# SCH_snow_light.net
KiCad netlist of a schematic drawn in EasyEDA
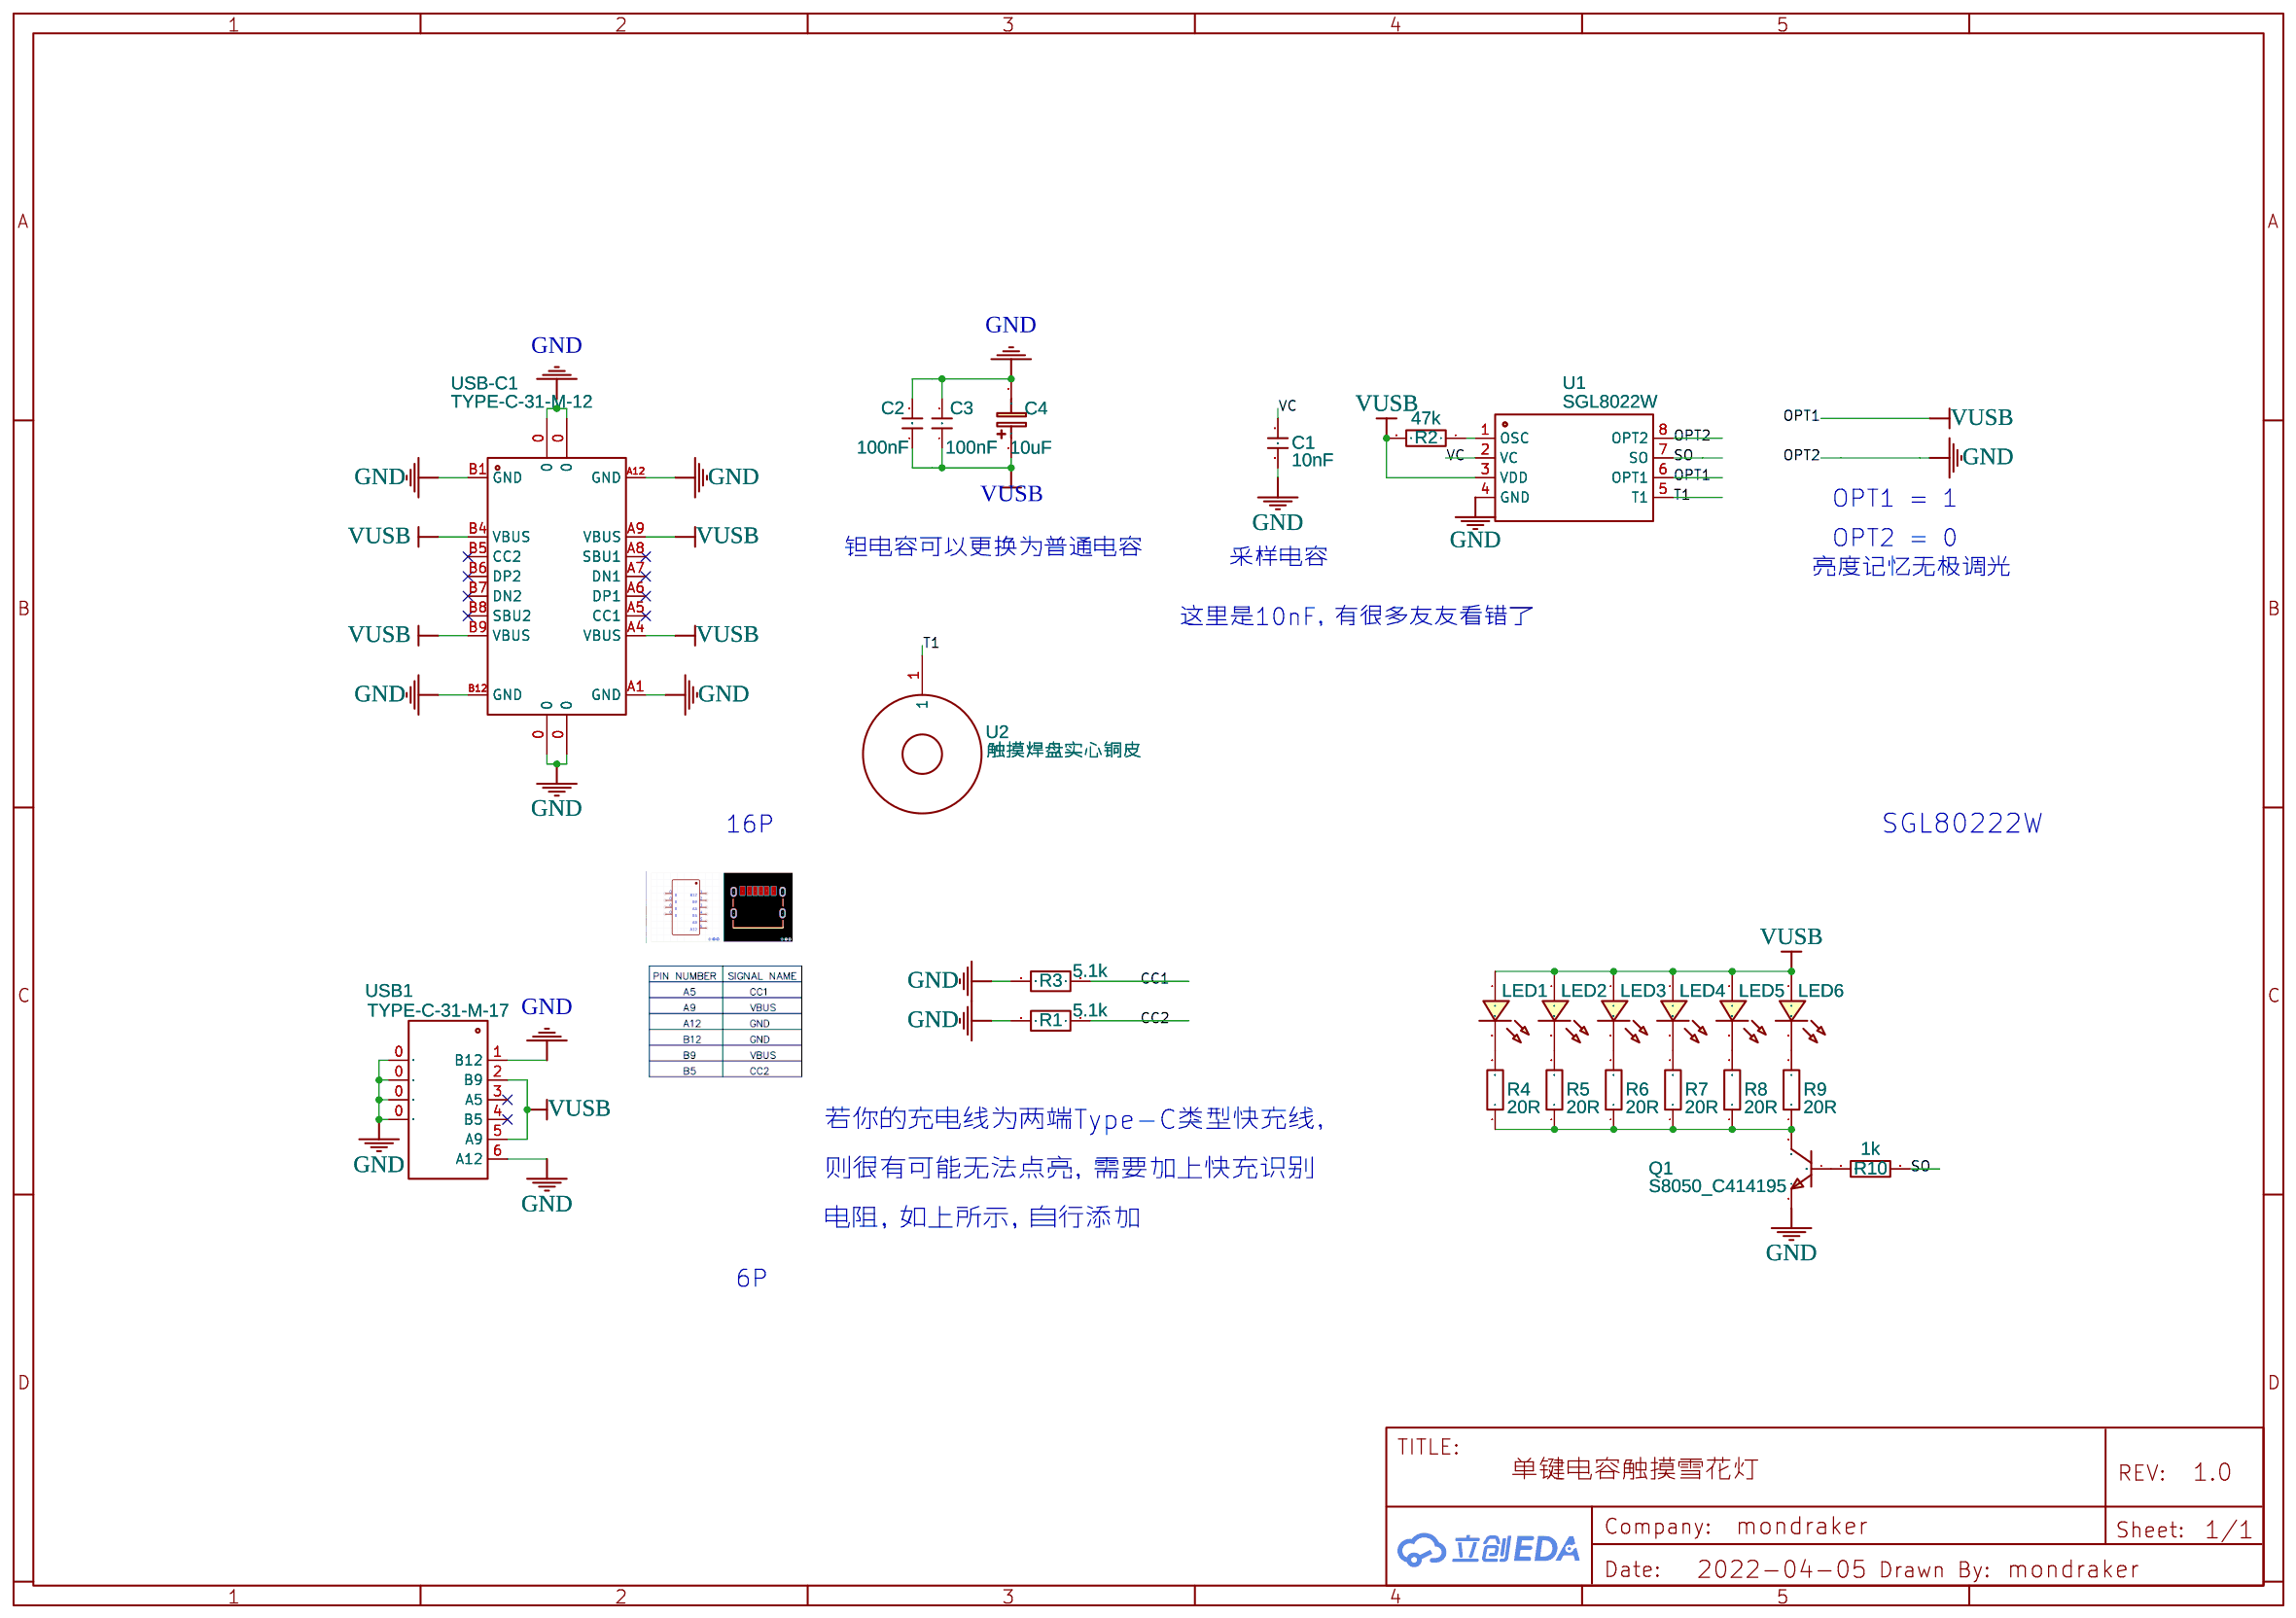
[diagram p0: schematic sheet]

(export (version "E")
  (design (tool "Eeschema 10.0.6"))
  (components
    (comp (ref "C1")
      (value "10nF")
      (fields
        (field (name "BOM_Manufacturer Part") "C0603C104K3RACAUTO")
        (field (name "BOM_Supplier Part") "C172738")
      )
      (libsource (lib "") (part "cap 0603"))
    )
    (comp (ref "C2")
      (value "100nF")
      (fields
        (field (name "BOM_Manufacturer Part") "C0603C104K3RACAUTO")
        (field (name "BOM_Supplier Part") "C172738")
      )
      (libsource (lib "") (part "cap 0603"))
    )
    (comp (ref "C3")
      (value "100nF")
      (fields
        (field (name "BOM_Manufacturer Part") "C0603C104K3RACAUTO")
        (field (name "BOM_Supplier Part") "C172738")
      )
      (libsource (lib "") (part "cap 0603"))
    )
    (comp (ref "C4") (value "10uF") (libsource (lib "") (part "C_Tan_SMD_A_EU")))
    (comp (ref "LED1") (value "3V 26MM") (libsource (lib "") (part "LED  26MM")))
    (comp (ref "LED2") (value "3V 26MM") (libsource (lib "") (part "LED  26MM")))
    (comp (ref "LED3") (value "3V 26MM") (libsource (lib "") (part "LED  26MM")))
    (comp (ref "LED4") (value "3V 26MM") (libsource (lib "") (part "LED  26MM")))
    (comp (ref "LED5") (value "3V 26MM") (libsource (lib "") (part "LED  26MM")))
    (comp (ref "LED6") (value "3V 26MM") (libsource (lib "") (part "LED  26MM")))
    (comp (ref "Q1")
      (value "S8050_C414195")
      (fields (field (name "BOM_Manufacturer Part") "S8050") (field (name "BOM_Supplier Part") "C414195"))
      (libsource (lib "") (part "S8050_C414195"))
    )
    (comp (ref "R1") (value "5.1k") (libsource (lib "") (part "R_0402_EU")))
    (comp (ref "R2")
      (value "47k")
      (fields
        (field (name "BOM_Manufacturer Part") "ARG03BTC3003")
        (field (name "BOM_Supplier Part") "C335091")
      )
      (libsource (lib "") (part "res-0603_2"))
    )
    (comp (ref "R3") (value "5.1k") (libsource (lib "") (part "R_0402_EU")))
    (comp (ref "R4")
      (value "20R")
      (fields
        (field (name "BOM_Manufacturer Part") "ARG03BTC3003")
        (field (name "BOM_Supplier Part") "C335091")
      )
      (libsource (lib "") (part "res-0603"))
    )
    (comp (ref "R5")
      (value "20R")
      (fields
        (field (name "BOM_Manufacturer Part") "ARG03BTC3003")
        (field (name "BOM_Supplier Part") "C335091")
      )
      (libsource (lib "") (part "res-0603"))
    )
    (comp (ref "R6")
      (value "20R")
      (fields
        (field (name "BOM_Manufacturer Part") "ARG03BTC3003")
        (field (name "BOM_Supplier Part") "C335091")
      )
      (libsource (lib "") (part "res-0603"))
    )
    (comp (ref "R7")
      (value "20R")
      (fields
        (field (name "BOM_Manufacturer Part") "ARG03BTC3003")
        (field (name "BOM_Supplier Part") "C335091")
      )
      (libsource (lib "") (part "res-0603"))
    )
    (comp (ref "R8")
      (value "20R")
      (fields
        (field (name "BOM_Manufacturer Part") "ARG03BTC3003")
        (field (name "BOM_Supplier Part") "C335091")
      )
      (libsource (lib "") (part "res-0603"))
    )
    (comp (ref "R9")
      (value "20R")
      (fields
        (field (name "BOM_Manufacturer Part") "ARG03BTC3003")
        (field (name "BOM_Supplier Part") "C335091")
      )
      (libsource (lib "") (part "res-0603"))
    )
    (comp (ref "R10")
      (value "1k")
      (fields
        (field (name "BOM_Manufacturer Part") "ARG03BTC3003")
        (field (name "BOM_Supplier Part") "C335091")
      )
      (libsource (lib "") (part "res-0603_1"))
    )
    (comp (ref "U1")
      (value "SGL8022W")
      (fields (field (name "BOM_Supplier Part") "C81650"))
      (libsource (lib "") (part "SGL8022W"))
    )
    (comp (ref "U2")
      (value "触摸焊盘实心铜皮")
      (fields (field (name "BOM_Manufacturer Part") "no"))
      (libsource (lib "") (part "触摸焊盘实心铜皮"))
    )
    (comp (ref "USB-C1")
      (value "TYPE-C-31-M-12")
      (fields (field (name "BOM_Supplier Part") "C165948"))
      (libsource (lib "") (part "TYPE-C-31-M-12"))
    )
    (comp (ref "USB1")
      (value "TYPE-C-31-M-17")
      (fields (field (name "BOM_Supplier Part") "C283540"))
      (libsource (lib "") (part "TYPE-C-31-M-17"))
    )
  )
  (nets
    (net (code "1") (name "/CC1") (class "Default")
      (node (ref "R3") (pin "1") (pinfunction "1_1") (pintype "unspecified"))
    )
    (net (code "2") (name "/CC2") (class "Default")
      (node (ref "R1") (pin "1") (pinfunction "1_1") (pintype "unspecified"))
    )
    (net (code "3") (name "/SO") (class "Default")
      (node (ref "R10") (pin "2") (pinfunction "2_2") (pintype "unspecified"))
      (node (ref "U1") (pin "7") (pinfunction "SO_7") (pintype "unspecified"))
    )
    (net (code "4") (name "/T1") (class "Default")
      (node (ref "U1") (pin "5") (pinfunction "T1_5") (pintype "unspecified"))
      (node (ref "U2") (pin "1") (pinfunction "1_1") (pintype "unspecified"))
    )
    (net (code "5") (name "/VC") (class "Default")
      (node (ref "C1") (pin "2") (pinfunction "2_2") (pintype "unspecified"))
      (node (ref "U1") (pin "2") (pinfunction "VC_2") (pintype "unspecified"))
    )
    (net (code "6") (name "GND") (class "Default")
      (node (ref "C1") (pin "1") (pinfunction "1_1") (pintype "unspecified"))
      (node (ref "C2") (pin "2") (pinfunction "2_2") (pintype "unspecified"))
      (node (ref "C3") (pin "2") (pinfunction "2_2") (pintype "unspecified"))
      (node (ref "C4") (pin "2") (pinfunction "2_2") (pintype "unspecified"))
      (node (ref "Q1") (pin "2") (pinfunction "E_2") (pintype "unspecified"))
      (node (ref "R1") (pin "2") (pinfunction "2_2") (pintype "unspecified"))
      (node (ref "R3") (pin "2") (pinfunction "2_2") (pintype "unspecified"))
      (node (ref "U1") (pin "4") (pinfunction "GND_4") (pintype "unspecified"))
      (node (ref "U1") (pin "8") (pinfunction "OPT2_8") (pintype "unspecified"))
      (node (ref "USB-C1") (pin "0") (pinfunction "0_0") (pintype "unspecified"))
      (node (ref "USB-C1") (pin "A1") (pinfunction "GND_A1") (pintype "unspecified"))
      (node (ref "USB-C1") (pin "A12") (pinfunction "GND_A12") (pintype "unspecified"))
      (node (ref "USB-C1") (pin "B1") (pinfunction "GND_B1") (pintype "unspecified"))
      (node (ref "USB-C1") (pin "B12") (pinfunction "GND_B12") (pintype "unspecified"))
      (node (ref "USB1") (pin "0") (pinfunction "0_0") (pintype "unspecified"))
      (node (ref "USB1") (pin "1") (pinfunction "B12_1") (pintype "unspecified"))
      (node (ref "USB1") (pin "6") (pinfunction "A12_6") (pintype "unspecified"))
    )
    (net (code "7") (name "Net-(LED1-Pad2)") (class "Default")
      (node (ref "LED1") (pin "2") (pinfunction "2_2") (pintype "unspecified"))
      (node (ref "R4") (pin "2") (pinfunction "2_2") (pintype "unspecified"))
    )
    (net (code "8") (name "Net-(LED2-Pad2)") (class "Default")
      (node (ref "LED2") (pin "2") (pinfunction "2_2") (pintype "unspecified"))
      (node (ref "R5") (pin "2") (pinfunction "2_2") (pintype "unspecified"))
    )
    (net (code "9") (name "Net-(LED3-Pad2)") (class "Default")
      (node (ref "LED3") (pin "2") (pinfunction "2_2") (pintype "unspecified"))
      (node (ref "R6") (pin "2") (pinfunction "2_2") (pintype "unspecified"))
    )
    (net (code "10") (name "Net-(LED4-Pad2)") (class "Default")
      (node (ref "LED4") (pin "2") (pinfunction "2_2") (pintype "unspecified"))
      (node (ref "R7") (pin "2") (pinfunction "2_2") (pintype "unspecified"))
    )
    (net (code "11") (name "Net-(LED5-Pad2)") (class "Default")
      (node (ref "LED5") (pin "2") (pinfunction "2_2") (pintype "unspecified"))
      (node (ref "R8") (pin "2") (pinfunction "2_2") (pintype "unspecified"))
    )
    (net (code "12") (name "Net-(LED6-Pad2)") (class "Default")
      (node (ref "LED6") (pin "2") (pinfunction "2_2") (pintype "unspecified"))
      (node (ref "R9") (pin "2") (pinfunction "2_2") (pintype "unspecified"))
    )
    (net (code "13") (name "Net-(Q1-B)") (class "Default")
      (node (ref "Q1") (pin "1") (pinfunction "B_1") (pintype "unspecified"))
      (node (ref "R10") (pin "1") (pinfunction "1_1") (pintype "unspecified"))
    )
    (net (code "14") (name "Net-(Q1-C)") (class "Default")
      (node (ref "Q1") (pin "3") (pinfunction "C_3") (pintype "unspecified"))
      (node (ref "R4") (pin "1") (pinfunction "1_1") (pintype "unspecified"))
      (node (ref "R5") (pin "1") (pinfunction "1_1") (pintype "unspecified"))
      (node (ref "R6") (pin "1") (pinfunction "1_1") (pintype "unspecified"))
      (node (ref "R7") (pin "1") (pinfunction "1_1") (pintype "unspecified"))
      (node (ref "R8") (pin "1") (pinfunction "1_1") (pintype "unspecified"))
      (node (ref "R9") (pin "1") (pinfunction "1_1") (pintype "unspecified"))
    )
    (net (code "15") (name "Net-(U1-OSC)") (class "Default")
      (node (ref "R2") (pin "1") (pinfunction "1_1") (pintype "unspecified"))
      (node (ref "U1") (pin "1") (pinfunction "OSC_1") (pintype "unspecified"))
    )
    (net (code "16") (name "VUSB") (class "Default")
      (node (ref "C2") (pin "1") (pinfunction "1_1") (pintype "unspecified"))
      (node (ref "C3") (pin "1") (pinfunction "1_1") (pintype "unspecified"))
      (node (ref "C4") (pin "1") (pinfunction "1_1") (pintype "unspecified"))
      (node (ref "LED1") (pin "1") (pinfunction "1_1") (pintype "unspecified"))
      (node (ref "LED2") (pin "1") (pinfunction "1_1") (pintype "unspecified"))
      (node (ref "LED3") (pin "1") (pinfunction "1_1") (pintype "unspecified"))
      (node (ref "LED4") (pin "1") (pinfunction "1_1") (pintype "unspecified"))
      (node (ref "LED5") (pin "1") (pinfunction "1_1") (pintype "unspecified"))
      (node (ref "LED6") (pin "1") (pinfunction "1_1") (pintype "unspecified"))
      (node (ref "R2") (pin "2") (pinfunction "2_2") (pintype "unspecified"))
      (node (ref "U1") (pin "3") (pinfunction "VDD_3") (pintype "unspecified"))
      (node (ref "U1") (pin "6") (pinfunction "OPT1_6") (pintype "unspecified"))
      (node (ref "USB-C1") (pin "A4") (pinfunction "VBUS_A4") (pintype "unspecified"))
      (node (ref "USB-C1") (pin "A9") (pinfunction "VBUS_A9") (pintype "unspecified"))
      (node (ref "USB-C1") (pin "B4") (pinfunction "VBUS_B4") (pintype "unspecified"))
      (node (ref "USB-C1") (pin "B9") (pinfunction "VBUS_B9") (pintype "unspecified"))
      (node (ref "USB1") (pin "2") (pinfunction "B9_2") (pintype "unspecified"))
      (node (ref "USB1") (pin "5") (pinfunction "A9_5") (pintype "unspecified"))
    )
    (net (code "17") (name "unconnected-(USB-C1-CC1-PadA5)") (class "Default")
      (node (ref "USB-C1") (pin "A5") (pinfunction "CC1_A5") (pintype "unspecified+no_connect"))
    )
    (net (code "18") (name "unconnected-(USB-C1-CC2-PadB5)") (class "Default")
      (node (ref "USB-C1") (pin "B5") (pinfunction "CC2_B5") (pintype "unspecified+no_connect"))
    )
    (net (code "19") (name "unconnected-(USB-C1-DN1-PadA7)") (class "Default")
      (node (ref "USB-C1") (pin "A7") (pinfunction "DN1_A7") (pintype "unspecified+no_connect"))
    )
    (net (code "20") (name "unconnected-(USB-C1-DN2-PadB7)") (class "Default")
      (node (ref "USB-C1") (pin "B7") (pinfunction "DN2_B7") (pintype "unspecified+no_connect"))
    )
    (net (code "21") (name "unconnected-(USB-C1-DP1-PadA6)") (class "Default")
      (node (ref "USB-C1") (pin "A6") (pinfunction "DP1_A6") (pintype "unspecified+no_connect"))
    )
    (net (code "22") (name "unconnected-(USB-C1-DP2-PadB6)") (class "Default")
      (node (ref "USB-C1") (pin "B6") (pinfunction "DP2_B6") (pintype "unspecified+no_connect"))
    )
    (net (code "23") (name "unconnected-(USB-C1-SBU1-PadA8)") (class "Default")
      (node (ref "USB-C1") (pin "A8") (pinfunction "SBU1_A8") (pintype "unspecified+no_connect"))
    )
    (net (code "24") (name "unconnected-(USB-C1-SBU2-PadB8)") (class "Default")
      (node (ref "USB-C1") (pin "B8") (pinfunction "SBU2_B8") (pintype "unspecified+no_connect"))
    )
    (net (code "25") (name "unconnected-(USB1-A5-Pad3)") (class "Default")
      (node (ref "USB1") (pin "3") (pinfunction "A5_3") (pintype "unspecified+no_connect"))
    )
    (net (code "26") (name "unconnected-(USB1-B5-Pad4)") (class "Default")
      (node (ref "USB1") (pin "4") (pinfunction "B5_4") (pintype "unspecified+no_connect"))
    )
  )
)
